# CAN.net
KiCad netlist of a schematic drawn in Altium Designer
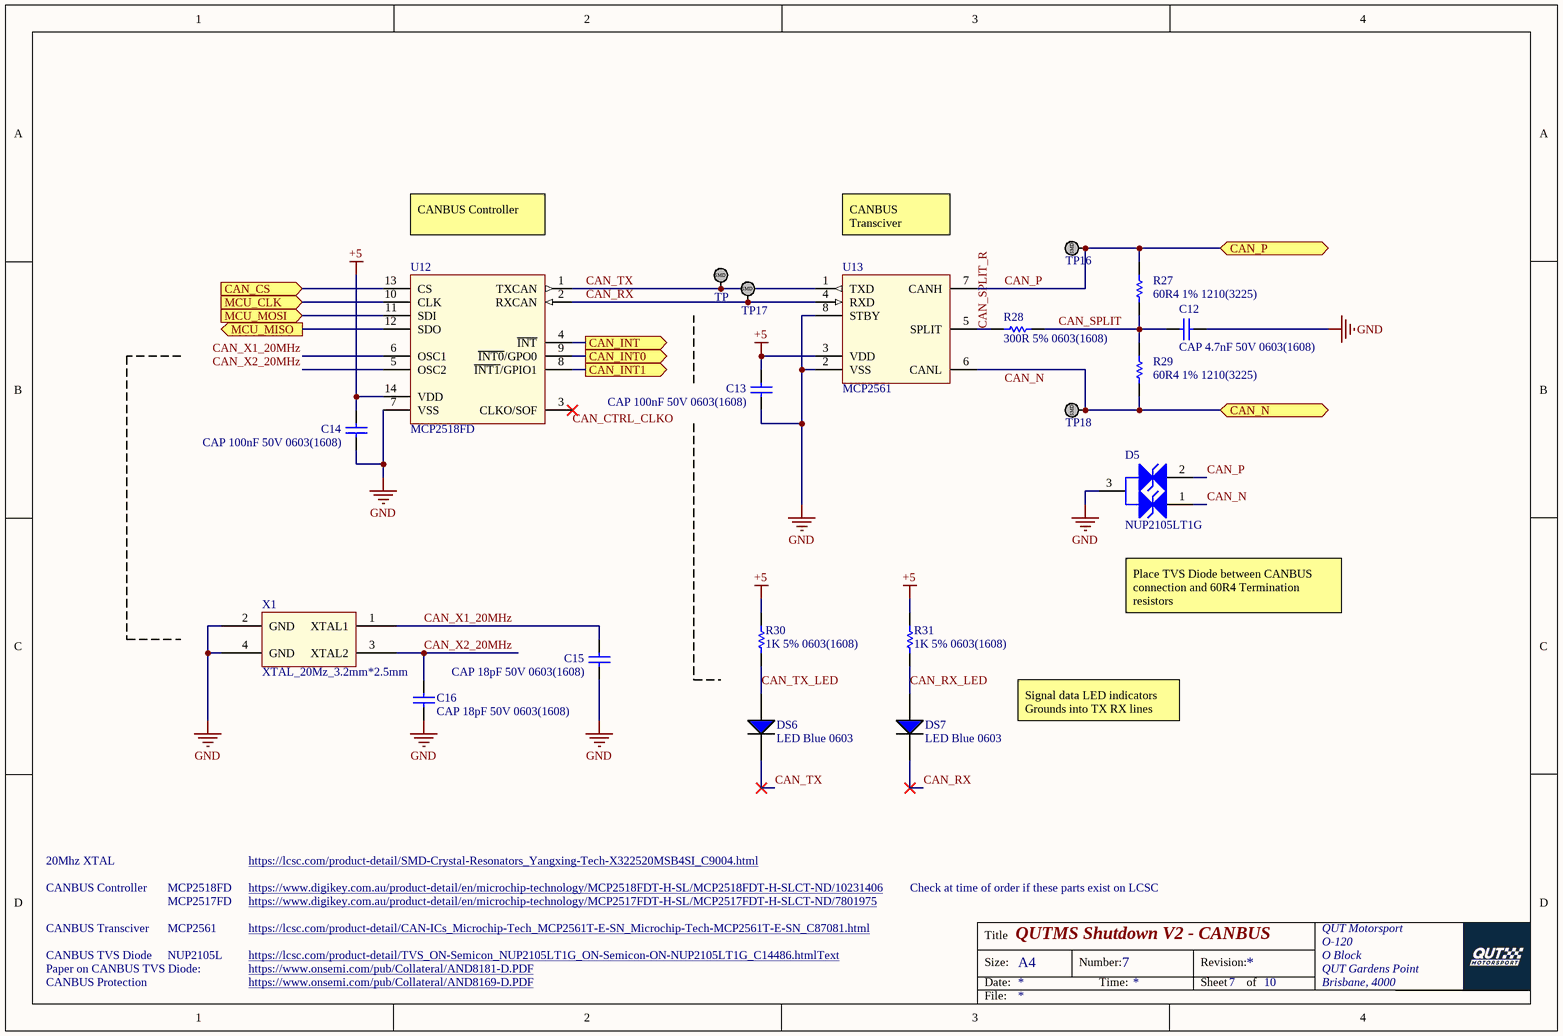
[diagram p0: CAN.SchDoc]

(export (version "E")
  (design (tool "Eeschema 10.0.6"))
  (components
    (comp (ref "C12")
      (value "CAP 4.7nF 50V 0603(1608)")
      (footprint "CAPC0603(1608)100_M")
      (description "CAP 4.7nF 50V ±5% 0603 (1608 Metric) Thickness 1mm SMD")
      (fields (field (name "TOLERANCE") "Â±5%"))
      (libsource (lib "Altium Content Vault") (part "CAP"))
    )
    (comp (ref "C13")
      (value "CAP 100nF 50V 0603(1608)")
      (footprint "CAPC0603(1608)100_L")
      (description "CAP 100nF 50V ±5% 0603 (1608 Metric) Thickness 1mm SMD")
      (fields (field (name "TOLERANCE") "Â±5%"))
      (libsource (lib "Altium Content Vault") (part "CAP"))
    )
    (comp (ref "C14")
      (value "CAP 100nF 50V 0603(1608)")
      (footprint "CAPC0603(1608)100_L")
      (description "CAP 100nF 50V ±5% 0603 (1608 Metric) Thickness 1mm SMD")
      (fields (field (name "TOLERANCE") "Â±5%"))
      (libsource (lib "Altium Content Vault") (part "CAP"))
    )
    (comp (ref "C15")
      (value "CAP 18pF 50V 0603(1608)")
      (footprint "CAPC0603(1608)100_L")
      (description "CAP 18pF 50V ±1% 0603 (1608 Metric) Thickness 1mm SMD")
      (fields (field (name "TOLERANCE") "Â±1%"))
      (libsource (lib "Altium Content Vault") (part "CAP"))
    )
    (comp (ref "C16")
      (value "CAP 18pF 50V 0603(1608)")
      (footprint "CAPC0603(1608)100_L")
      (description "CAP 18pF 50V ±1% 0603 (1608 Metric) Thickness 1mm SMD")
      (fields (field (name "TOLERANCE") "Â±1%"))
      (libsource (lib "Altium Content Vault") (part "CAP"))
    )
    (comp (ref "D5")
      (value "NUP2105LT1G")
      (footprint "ONSC-SOT-23-3-318-08_V")
      (description "Dual Line CAN Bus Protector, 3-Pin SOT-23, Pb-Free, Tape and Reel")
      (fields (field (name "MANUFACTURER") "On Semiconductor"))
      (libsource (lib "Altium Content Vault") (part "ONSC-NUP21X5X-SOT-23-3-318-08"))
    )
    (comp (ref "DS6")
      (value "LED Blue 0603")
      (footprint "LED BLUE 0603")
      (libsource (lib "QUTMS_LEDLibrary") (part "LED BLUE 0603"))
    )
    (comp (ref "DS7")
      (value "LED Blue 0603")
      (footprint "LED BLUE 0603")
      (libsource (lib "QUTMS_LEDLibrary") (part "LED BLUE 0603"))
    )
    (comp (ref "R27")
      (value "60R4 1% 1210(3225)")
      (footprint "RESC1210(3225)_L")
      (description "60R4 0.5W 1% 1210 (3225 Metric)  SMD")
      (fields (field (name "TOLERANCE") "1 %") (field (name "POWER") "0.5 W"))
      (libsource (lib "Altium Content Vault") (part "RES"))
    )
    (comp (ref "R28")
      (value "300R 5% 0603(1608)")
      (footprint "RESC0603(1608)_N")
      (description "300R 0.1W 5% 0603 (1608 Metric)  SMD")
      (fields (field (name "TOLERANCE") "5 %") (field (name "POWER") "0.1 W"))
      (libsource (lib "Altium Content Vault") (part "RES"))
    )
    (comp (ref "R29")
      (value "60R4 1% 1210(3225)")
      (footprint "RESC1210(3225)_L")
      (description "60R4 0.5W 1% 1210 (3225 Metric)  SMD")
      (fields (field (name "TOLERANCE") "1 %") (field (name "POWER") "0.5 W"))
      (libsource (lib "Altium Content Vault") (part "RES"))
    )
    (comp (ref "R30")
      (value "1K 5% 0603(1608)")
      (footprint "RESC0603(1608)_L")
      (description "1K 0.1W 5% 0603 (1608 Metric)  SMD")
      (fields (field (name "TOLERANCE") "5 %") (field (name "POWER") "0.1 W"))
      (libsource (lib "Altium Content Vault") (part "RES"))
    )
    (comp (ref "R31")
      (value "1K 5% 0603(1608)")
      (footprint "RESC0603(1608)_L")
      (description "1K 0.1W 5% 0603 (1608 Metric)  SMD")
      (fields (field (name "TOLERANCE") "5 %") (field (name "POWER") "0.1 W"))
      (libsource (lib "Altium Content Vault") (part "RES"))
    )
    (comp (ref "TP")
      (value "TestPoint_SMD")
      (footprint "TestPointSMD")
      (libsource (lib "StandardTest") (part "TestPoint_SMD"))
    )
    (comp (ref "TP16")
      (value "TestPoint_SMD")
      (footprint "TestPointSMD")
      (libsource (lib "StandardTest") (part "TestPoint_SMD"))
    )
    (comp (ref "TP17")
      (value "TestPoint_SMD")
      (footprint "TestPointSMD")
      (libsource (lib "StandardTest") (part "TestPoint_SMD"))
    )
    (comp (ref "TP18")
      (value "TestPoint_SMD")
      (footprint "TestPointSMD")
      (libsource (lib "StandardTest") (part "TestPoint_SMD"))
    )
    (comp (ref "U12")
      (value "MCP2518FD")
      (footprint "MCP2517FD SOIC")
      (libsource (lib "QUTMS_CANLibrary") (part "MCP2518FD"))
    )
    (comp (ref "U13")
      (value "MCP2561")
      (footprint "MCP2561 SOIC")
      (libsource (lib "QUTMS_CANLibrary") (part "MCP2561"))
    )
    (comp (ref "X1")
      (value "XTAL_20Mz_3.2mm*2.5mm")
      (footprint "3.2mm*2.5mm")
      (libsource (lib "QUTMS_CrystalLibrary") (part "XTAL_20Mz_3.2mm*2.5mm"))
    )
  )
  (nets
    (net (code "1") (name "+5") (class "Default")
      (node (ref "C13") (pin "2") (pinfunction "2_2") (pintype "passive"))
      (node (ref "C14") (pin "2") (pinfunction "2_2") (pintype "passive"))
      (node (ref "R30") (pin "2") (pinfunction "2_2") (pintype "passive"))
      (node (ref "R31") (pin "2") (pinfunction "2_2") (pintype "passive"))
      (node (ref "U12") (pin "14") (pinfunction "VDD_14") (pintype "passive"))
      (node (ref "U13") (pin "3") (pinfunction "VDD_3") (pintype "passive"))
    )
    (net (code "2") (name "/CAN_CS") (class "Default")
      (node (ref "U12") (pin "13") (pinfunction "CS_13") (pintype "passive"))
    )
    (net (code "3") (name "/CAN_CTRL_CLKO") (class "Default")
      (node (ref "U12") (pin "3") (pinfunction "CLKO/SOF_3") (pintype "passive+no_connect"))
    )
    (net (code "4") (name "/CAN_INT") (class "Default")
      (node (ref "U12") (pin "4") (pinfunction "~{INT}_4") (pintype "passive"))
    )
    (net (code "5") (name "/CAN_INT0") (class "Default")
      (node (ref "U12") (pin "9") (pinfunction "~{INT0}/GPO0_9") (pintype "passive"))
    )
    (net (code "6") (name "/CAN_INT1") (class "Default")
      (node (ref "U12") (pin "8") (pinfunction "~{INT1}/GPIO1_8") (pintype "passive"))
    )
    (net (code "7") (name "/CAN_N") (class "Default")
      (node (ref "D5") (pin "1") (pinfunction "K_1") (pintype "passive"))
      (node (ref "R29") (pin "1") (pinfunction "1_1") (pintype "passive"))
      (node (ref "TP18") (pin "1") (pinfunction "1_1") (pintype "passive"))
      (node (ref "U13") (pin "6") (pinfunction "CANL_6") (pintype "passive"))
    )
    (net (code "8") (name "/CAN_P") (class "Default")
      (node (ref "D5") (pin "2") (pinfunction "K_2") (pintype "passive"))
      (node (ref "R27") (pin "2") (pinfunction "2_2") (pintype "passive"))
      (node (ref "TP16") (pin "1") (pinfunction "1_1") (pintype "passive"))
      (node (ref "U13") (pin "7") (pinfunction "CANH_7") (pintype "passive"))
    )
    (net (code "9") (name "/CAN_RX") (class "Default")
      (node (ref "DS7") (pin "2") (pinfunction "C_2") (pintype "passive"))
      (node (ref "TP17") (pin "1") (pinfunction "1_1") (pintype "passive"))
      (node (ref "U12") (pin "2") (pinfunction "RXCAN_2") (pintype "input"))
      (node (ref "U13") (pin "4") (pinfunction "RXD_4") (pintype "input"))
    )
    (net (code "10") (name "/CAN_RX_LED") (class "Default")
      (node (ref "DS7") (pin "1") (pinfunction "A_1") (pintype "passive"))
      (node (ref "R31") (pin "1") (pinfunction "1_1") (pintype "passive"))
    )
    (net (code "11") (name "/CAN_SPLIT") (class "Default")
      (node (ref "C12") (pin "2") (pinfunction "2_2") (pintype "passive"))
      (node (ref "R27") (pin "1") (pinfunction "1_1") (pintype "passive"))
      (node (ref "R28") (pin "2") (pinfunction "2_2") (pintype "passive"))
      (node (ref "R29") (pin "2") (pinfunction "2_2") (pintype "passive"))
    )
    (net (code "12") (name "/CAN_SPLIT_R") (class "Default")
      (node (ref "R28") (pin "1") (pinfunction "1_1") (pintype "passive"))
      (node (ref "U13") (pin "5") (pinfunction "SPLIT_5") (pintype "passive"))
    )
    (net (code "13") (name "/CAN_TX") (class "Default")
      (node (ref "DS6") (pin "2") (pinfunction "C_2") (pintype "passive"))
      (node (ref "TP") (pin "1") (pinfunction "1_1") (pintype "passive"))
      (node (ref "U12") (pin "1") (pinfunction "TXCAN_1") (pintype "output"))
      (node (ref "U13") (pin "1") (pinfunction "TXD_1") (pintype "output"))
    )
    (net (code "14") (name "/CAN_TX_LED") (class "Default")
      (node (ref "DS6") (pin "1") (pinfunction "A_1") (pintype "passive"))
      (node (ref "R30") (pin "1") (pinfunction "1_1") (pintype "passive"))
    )
    (net (code "15") (name "/CAN_X1_20MHz") (class "Default")
      (node (ref "C15") (pin "2") (pinfunction "2_2") (pintype "passive"))
      (node (ref "U12") (pin "6") (pinfunction "OSC1_6") (pintype "passive"))
      (node (ref "X1") (pin "1") (pinfunction "XTAL1_1") (pintype "passive"))
    )
    (net (code "16") (name "/CAN_X2_20MHz") (class "Default")
      (node (ref "C16") (pin "2") (pinfunction "2_2") (pintype "passive"))
      (node (ref "U12") (pin "5") (pinfunction "OSC2_5") (pintype "passive"))
      (node (ref "X1") (pin "3") (pinfunction "XTAL2_3") (pintype "passive"))
    )
    (net (code "17") (name "/MCU_CLK") (class "Default")
      (node (ref "U12") (pin "10") (pinfunction "CLK_10") (pintype "passive"))
    )
    (net (code "18") (name "/MCU_MISO") (class "Default")
      (node (ref "U12") (pin "12") (pinfunction "SDO_12") (pintype "passive"))
    )
    (net (code "19") (name "/MCU_MOSI") (class "Default")
      (node (ref "U12") (pin "11") (pinfunction "SDI_11") (pintype "passive"))
    )
    (net (code "20") (name "GND") (class "Default")
      (node (ref "C12") (pin "1") (pinfunction "1_1") (pintype "passive"))
      (node (ref "C13") (pin "1") (pinfunction "1_1") (pintype "passive"))
      (node (ref "C14") (pin "1") (pinfunction "1_1") (pintype "passive"))
      (node (ref "C15") (pin "1") (pinfunction "1_1") (pintype "passive"))
      (node (ref "C16") (pin "1") (pinfunction "1_1") (pintype "passive"))
      (node (ref "D5") (pin "3") (pinfunction "K_3") (pintype "passive"))
      (node (ref "U12") (pin "7") (pinfunction "VSS_7") (pintype "passive"))
      (node (ref "U13") (pin "2") (pinfunction "VSS_2") (pintype "passive"))
      (node (ref "U13") (pin "8") (pinfunction "STBY_8") (pintype "passive"))
      (node (ref "X1") (pin "2") (pinfunction "GND_2") (pintype "passive"))
      (node (ref "X1") (pin "4") (pinfunction "GND_4") (pintype "passive"))
    )
  )
)
